# TTL_TO_RS232.net
KiCad netlist of a schematic drawn in Altium Designer
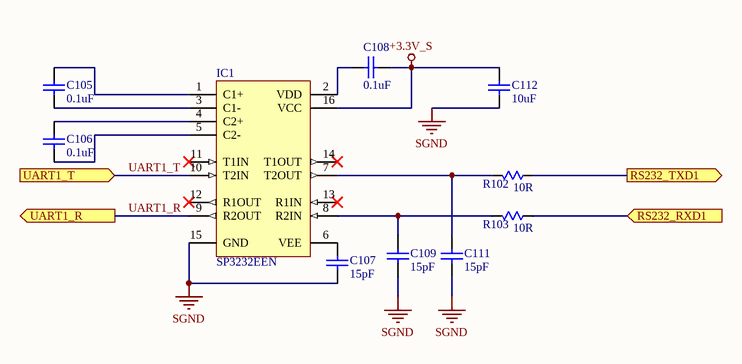
[diagram p0: TTL_TO_RS232.SchDoc]

(export (version "E")
  (design (tool "Eeschema 10.0.6"))
  (components
    (comp (ref "C105")
      (value "0.1uF")
      (footprint "C0805")
      (description "CAP")
      (fields (field (name "PUBLISHER") "Altium Limited"))
      (libsource (lib "Passive Components Class") (part "CAP"))
    )
    (comp (ref "C106")
      (value "0.1uF")
      (footprint "C0805")
      (description "CAP")
      (fields (field (name "PUBLISHER") "Altium Limited"))
      (libsource (lib "Passive Components Class") (part "CAP"))
    )
    (comp (ref "C107")
      (value "15pF")
      (footprint "C0805")
      (description "Capacitor")
      (fields (field (name "PUBLISHER") "Altium Limited"))
      (libsource (lib "Miscellaneous Devices") (part "Cap"))
    )
    (comp (ref "C108")
      (value "0.1uF")
      (footprint "C0805")
      (description "CAP")
      (fields (field (name "PUBLISHER") "Altium Limited"))
      (libsource (lib "Passive Components Class") (part "CAP"))
    )
    (comp (ref "C109")
      (value "15pF")
      (footprint "C0805")
      (description "Capacitor")
      (fields (field (name "PUBLISHER") "Altium Limited"))
      (libsource (lib "Miscellaneous Devices") (part "Cap"))
    )
    (comp (ref "C111")
      (value "15pF")
      (footprint "C0805")
      (description "Capacitor")
      (fields (field (name "PUBLISHER") "Altium Limited"))
      (libsource (lib "Miscellaneous Devices") (part "Cap"))
    )
    (comp (ref "C112")
      (value "10uF")
      (footprint "C1206")
      (description "CAP")
      (fields (field (name "PUBLISHER") "Altium Limited"))
      (libsource (lib "Passive Components Class") (part "CAP"))
    )
    (comp (ref "IC1")
      (value "SP3232EEN")
      (footprint "SO16-150")
      (description "+5V Powered, Multi-Channel RS-232 Driver/Receiver")
      (fields
        (field (name "MANUFACTURER") "Maxim")
        (field (name "PUBLISHER") "Altium Hobart Technology Centre")
      )
      (libsource (lib "Maxim Communication Transceiver") (part "MAX232ACPE"))
    )
    (comp (ref "R102")
      (value "10R")
      (footprint "R0805")
      (description "Resistor")
      (fields (field (name "PUBLISHER") "Altium Limited"))
      (libsource (lib "Passive Components Class") (part "Res"))
    )
    (comp (ref "R103")
      (value "10R")
      (footprint "R0805")
      (description "Resistor")
      (fields (field (name "PUBLISHER") "Altium Limited"))
      (libsource (lib "Temp") (part "Res"))
    )
  )
  (nets
    (net (code "1") (name "+3.3V_S") (class "Default")
      (node (ref "C108") (pin "1") (pinfunction "1_1") (pintype "passive"))
      (node (ref "C112") (pin "2") (pinfunction "2_2") (pintype "passive"))
      (node (ref "IC1") (pin "16") (pinfunction "VCC_16") (pintype "power_in"))
    )
    (net (code "2") (name "/RS232_RXD1") (class "Default")
      (node (ref "R103") (pin "2") (pinfunction "2_2") (pintype "passive"))
    )
    (net (code "3") (name "/RS232_TXD1") (class "Default")
      (node (ref "R102") (pin "2") (pinfunction "2_2") (pintype "passive"))
    )
    (net (code "4") (name "/UART1_R") (class "Default")
      (node (ref "IC1") (pin "9") (pinfunction "R2OUT_9") (pintype "output"))
    )
    (net (code "5") (name "/UART1_T") (class "Default")
      (node (ref "IC1") (pin "10") (pinfunction "T2IN_10") (pintype "input"))
    )
    (net (code "6") (name "Net-(IC1-C1+)") (class "Default")
      (node (ref "C105") (pin "2") (pinfunction "2_2") (pintype "passive"))
      (node (ref "IC1") (pin "1") (pinfunction "C1+_1") (pintype "passive"))
    )
    (net (code "7") (name "Net-(IC1-C1-)") (class "Default")
      (node (ref "C105") (pin "1") (pinfunction "1_1") (pintype "passive"))
      (node (ref "IC1") (pin "3") (pinfunction "C1-_3") (pintype "passive"))
    )
    (net (code "8") (name "Net-(IC1-C2+)") (class "Default")
      (node (ref "C106") (pin "2") (pinfunction "2_2") (pintype "passive"))
      (node (ref "IC1") (pin "4") (pinfunction "C2+_4") (pintype "passive"))
    )
    (net (code "9") (name "Net-(IC1-C2-)") (class "Default")
      (node (ref "C106") (pin "1") (pinfunction "1_1") (pintype "passive"))
      (node (ref "IC1") (pin "5") (pinfunction "C2-_5") (pintype "passive"))
    )
    (net (code "10") (name "Net-(IC1-R2IN)") (class "Default")
      (node (ref "C109") (pin "1") (pinfunction "1_1") (pintype "passive"))
      (node (ref "IC1") (pin "8") (pinfunction "R2IN_8") (pintype "input"))
      (node (ref "R103") (pin "1") (pinfunction "1_1") (pintype "passive"))
    )
    (net (code "11") (name "Net-(IC1-T2OUT)") (class "Default")
      (node (ref "C111") (pin "1") (pinfunction "1_1") (pintype "passive"))
      (node (ref "IC1") (pin "7") (pinfunction "T2OUT_7") (pintype "output"))
      (node (ref "R102") (pin "1") (pinfunction "1_1") (pintype "passive"))
    )
    (net (code "12") (name "Net-(IC1-VDD)") (class "Default")
      (node (ref "C108") (pin "2") (pinfunction "2_2") (pintype "passive"))
      (node (ref "IC1") (pin "2") (pinfunction "VDD_2") (pintype "power_in"))
    )
    (net (code "13") (name "Net-(IC1-VEE)") (class "Default")
      (node (ref "C107") (pin "1") (pinfunction "1_1") (pintype "passive"))
      (node (ref "IC1") (pin "6") (pinfunction "VEE_6") (pintype "power_in"))
    )
    (net (code "14") (name "SGND") (class "Default")
      (node (ref "C107") (pin "2") (pinfunction "2_2") (pintype "passive"))
      (node (ref "C109") (pin "2") (pinfunction "2_2") (pintype "passive"))
      (node (ref "C111") (pin "2") (pinfunction "2_2") (pintype "passive"))
      (node (ref "C112") (pin "1") (pinfunction "1_1") (pintype "passive"))
      (node (ref "IC1") (pin "15") (pinfunction "GND_15") (pintype "power_in"))
    )
    (net (code "15") (name "unconnected-(IC1-R1IN-Pad13)") (class "Default")
      (node (ref "IC1") (pin "13") (pinfunction "R1IN_13") (pintype "input+no_connect"))
    )
    (net (code "16") (name "unconnected-(IC1-R1OUT-Pad12)") (class "Default")
      (node (ref "IC1") (pin "12") (pinfunction "R1OUT_12") (pintype "output+no_connect"))
    )
    (net (code "17") (name "unconnected-(IC1-T1IN-Pad11)") (class "Default")
      (node (ref "IC1") (pin "11") (pinfunction "T1IN_11") (pintype "input+no_connect"))
    )
    (net (code "18") (name "unconnected-(IC1-T1OUT-Pad14)") (class "Default")
      (node (ref "IC1") (pin "14") (pinfunction "T1OUT_14") (pintype "output+no_connect"))
    )
  )
)
